# Schematic.net
KiCad netlist of a schematic drawn in Altium Designer
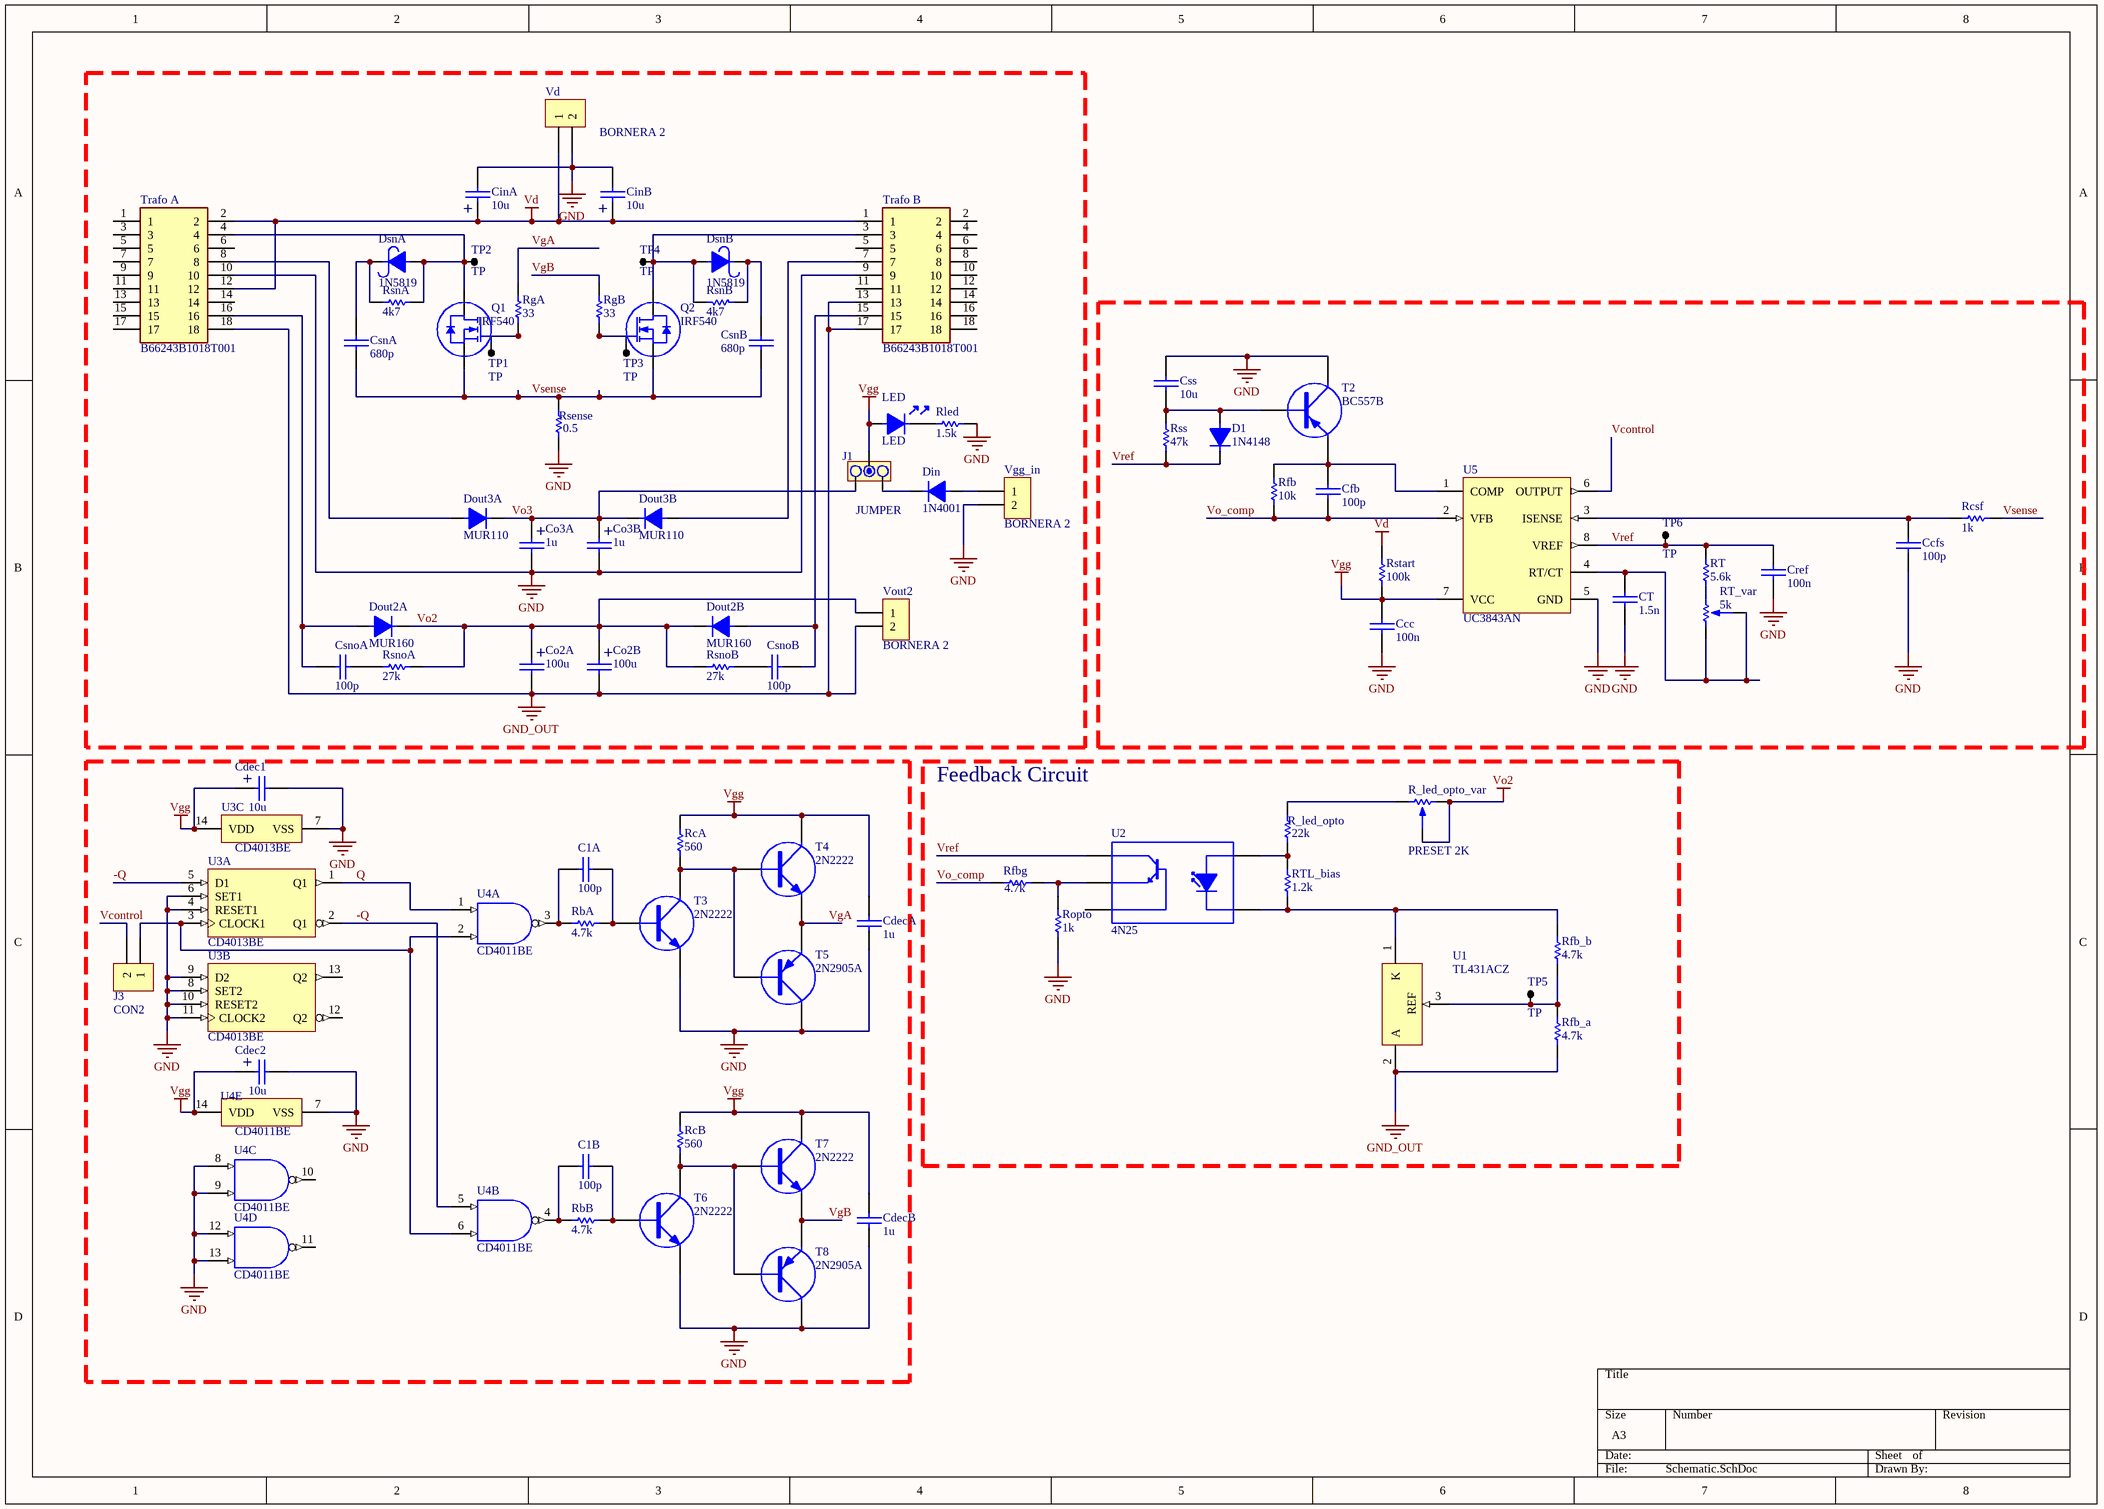
[diagram p0: Schematic.SchDoc]

(export (version "E")
  (design (tool "Eeschema 10.0.6"))
  (components
    (comp (ref "C1A") (value "100p") (footprint "CAP100") (libsource (lib "LIBEBAL Tobi") (part "CAP")))
    (comp (ref "C1B") (value "100p") (footprint "CAP100") (libsource (lib "LIBEBAL Tobi") (part "CAP")))
    (comp (ref "Ccc") (value "100n") (footprint "CAP100") (libsource (lib "LIBEBAL Tobi") (part "CAP")))
    (comp (ref "Ccfs") (value "100p") (footprint "CAP100") (libsource (lib "LIBEBAL Tobi") (part "CAP")))
    (comp (ref "Cdec1") (value "10u") (footprint "CAP100RP2") (libsource (lib "LIBEBAL") (part "CAPPOL")))
    (comp (ref "Cdec2") (value "10u") (footprint "CAP100RP2") (libsource (lib "LIBEBAL") (part "CAPPOL")))
    (comp (ref "CdecA") (value "1u") (footprint "CAP200") (libsource (lib "LIBEBAL Tobi") (part "CAP")))
    (comp (ref "CdecB") (value "1u") (footprint "CAP200") (libsource (lib "LIBEBAL Tobi") (part "CAP")))
    (comp (ref "Cfb") (value "100p") (footprint "CAP100") (libsource (lib "LIBEBAL Tobi") (part "CAP")))
    (comp (ref "CinA") (value "10u") (footprint "CAP100RP") (libsource (lib "LIBEBAL") (part "CAPPOL")))
    (comp (ref "CinB") (value "10u") (footprint "CAP100RP") (libsource (lib "LIBEBAL") (part "CAPPOL")))
    (comp (ref "Co2A") (value "100u") (footprint "CAP300RP") (libsource (lib "LIBEBAL") (part "CAPPOL")))
    (comp (ref "Co2B") (value "100u") (footprint "CAP300RP") (libsource (lib "LIBEBAL") (part "CAPPOL")))
    (comp (ref "Co3A") (value "1u") (footprint "CAP100RP") (libsource (lib "LIBEBAL") (part "CAPPOL")))
    (comp (ref "Co3B") (value "1u") (footprint "CAP100RP") (libsource (lib "LIBEBAL") (part "CAPPOL")))
    (comp (ref "Cref") (value "100n") (footprint "CAP100") (libsource (lib "LIBEBAL Tobi") (part "CAP")))
    (comp (ref "CsnA") (value "680p") (footprint "CAP200") (libsource (lib "LIBEBAL Tobi") (part "CAP")))
    (comp (ref "CsnB") (value "680p") (footprint "CAP200") (libsource (lib "LIBEBAL Tobi") (part "CAP")))
    (comp (ref "CsnoA") (value "100p") (footprint "CAP100") (libsource (lib "LIBEBAL Tobi") (part "CAP")))
    (comp (ref "CsnoB") (value "100p") (footprint "CAP100") (libsource (lib "LIBEBAL Tobi") (part "CAP")))
    (comp (ref "Css") (value "10u") (footprint "CAP100") (libsource (lib "LIBEBAL Tobi") (part "CAP")))
    (comp (ref "CT") (value "1.5n") (footprint "CAP100") (libsource (lib "LIBEBAL Tobi") (part "CAP")))
    (comp (ref "D1") (value "1N4148") (footprint "DO41") (libsource (lib "LIBEBAL") (part "DIODO")))
    (comp (ref "Din") (value "1N4001") (footprint "DO41") (libsource (lib "LIBEBAL") (part "DIODO")))
    (comp (ref "Dout2A") (value "MUR160") (footprint "DO41") (libsource (lib "LIBEBAL") (part "DIODO")))
    (comp (ref "Dout2B") (value "MUR160") (footprint "DO41") (libsource (lib "LIBEBAL") (part "DIODO")))
    (comp (ref "Dout3A") (value "MUR110") (footprint "DO41") (libsource (lib "LIBEBAL") (part "DIODO")))
    (comp (ref "Dout3B") (value "MUR110") (footprint "DO41") (libsource (lib "LIBEBAL") (part "DIODO")))
    (comp (ref "DsnA") (value "1N5819") (footprint "DO41") (libsource (lib "") (part "DIODO SCHOTTKY_1")))
    (comp (ref "DsnB")
      (value "1N5819")
      (footprint "DO41")
      (libsource (lib "LIBEBAL") (part "DIODO SCHOTTKY"))
    )
    (comp (ref "J1") (value "JUMPER") (footprint "JUMPER3") (libsource (lib "LIBEBAL") (part "JUMPER3")))
    (comp (ref "J3") (value "CON2") (footprint "SIP2") (libsource (lib "LIBEBAL") (part "CON2")))
    (comp (ref "LED") (value "LED") (footprint "LED3") (libsource (lib "LIBEBAL") (part "LED")))
    (comp (ref "Q1") (value "IRF540") (footprint "TO-220 V") (libsource (lib "LIBEBAL") (part "MOSFET N")))
    (comp (ref "Q2") (value "IRF540") (footprint "TO-220 V") (libsource (lib "LIBEBAL") (part "MOSFET N")))
    (comp (ref "RbA") (value "4.7k") (footprint "RES400") (libsource (lib "LIBEBAL Tobi") (part "RES")))
    (comp (ref "RbB") (value "4.7k") (footprint "RES400") (libsource (lib "LIBEBAL Tobi") (part "RES")))
    (comp (ref "RcA") (value "560") (footprint "RES400") (libsource (lib "LIBEBAL Tobi") (part "RES")))
    (comp (ref "RcB") (value "560") (footprint "RES400") (libsource (lib "LIBEBAL Tobi") (part "RES")))
    (comp (ref "Rcsf") (value "1k") (footprint "RES400") (libsource (lib "LIBEBAL Tobi") (part "RES")))
    (comp (ref "Rfb") (value "10k") (footprint "RES400") (libsource (lib "LIBEBAL Tobi") (part "RES")))
    (comp (ref "Rfbg") (value "4.7k") (footprint "RES400") (libsource (lib "LIBEBAL Tobi") (part "RES")))
    (comp (ref "Rfb_a") (value "4.7k") (footprint "RES400") (libsource (lib "LIBEBAL Tobi") (part "RES")))
    (comp (ref "Rfb_b") (value "4.7k") (footprint "RES400") (libsource (lib "LIBEBAL Tobi") (part "RES")))
    (comp (ref "RgA") (value "33") (footprint "RES400") (libsource (lib "LIBEBAL Tobi") (part "RES")))
    (comp (ref "RgB") (value "33") (footprint "RES400") (libsource (lib "LIBEBAL Tobi") (part "RES")))
    (comp (ref "Rled") (value "1.5k") (footprint "RES400") (libsource (lib "LIBEBAL Tobi") (part "RES")))
    (comp (ref "Ropto") (value "1k") (footprint "RES400") (libsource (lib "LIBEBAL Tobi") (part "RES")))
    (comp (ref "Rsense") (value "0.5") (footprint "RES400") (libsource (lib "LIBEBAL Tobi") (part "RES")))
    (comp (ref "RsnA") (value "4k7") (footprint "RES600") (libsource (lib "LIBEBAL Tobi") (part "RES")))
    (comp (ref "RsnB") (value "4k7") (footprint "RES600") (libsource (lib "LIBEBAL Tobi") (part "RES")))
    (comp (ref "RsnoA") (value "27k") (footprint "RES600") (libsource (lib "LIBEBAL Tobi") (part "RES")))
    (comp (ref "RsnoB") (value "27k") (footprint "RES600") (libsource (lib "LIBEBAL Tobi") (part "RES")))
    (comp (ref "Rss") (value "47k") (footprint "RES400") (libsource (lib "LIBEBAL Tobi") (part "RES")))
    (comp (ref "Rstart") (value "100k") (footprint "RES400") (libsource (lib "LIBEBAL Tobi") (part "RES")))
    (comp (ref "RT") (value "5.6k") (footprint "RES400") (libsource (lib "LIBEBAL Tobi") (part "RES")))
    (comp (ref "RTL_bias") (value "1.2k") (footprint "RES400") (libsource (lib "LIBEBAL Tobi") (part "RES")))
    (comp (ref "RT_var") (value "5k") (footprint "PRESET V") (libsource (lib "LIBEBAL Tobi") (part "PRESET")))
    (comp (ref "R_led_opto") (value "22k") (footprint "RES600") (libsource (lib "LIBEBAL Tobi") (part "RES")))
    (comp (ref "R_led_opto_var")
      (value "PRESET 2K")
      (footprint "PRESET H")
      (libsource (lib "LIBEBAL") (part "PRESET"))
    )
    (comp (ref "T2") (value "BC557B") (footprint "TO92") (libsource (lib "LIBEBAL") (part "TRANSISTOR PNP")))
    (comp (ref "T3") (value "2N2222") (footprint "TO92") (libsource (lib "LIBEBAL") (part "TRANSISTOR NPN")))
    (comp (ref "T4") (value "2N2222") (footprint "TO92") (libsource (lib "LIBEBAL") (part "TRANSISTOR NPN")))
    (comp (ref "T5") (value "2N2905A") (footprint "TO92") (libsource (lib "LIBEBAL") (part "TRANSISTOR PNP")))
    (comp (ref "T6") (value "2N2222") (footprint "TO92") (libsource (lib "LIBEBAL") (part "TRANSISTOR NPN")))
    (comp (ref "T7") (value "2N2222") (footprint "TO92") (libsource (lib "LIBEBAL") (part "TRANSISTOR NPN")))
    (comp (ref "T8") (value "2N2905A") (footprint "TO92") (libsource (lib "LIBEBAL") (part "TRANSISTOR PNP")))
    (comp (ref "TP1") (value "TP") (footprint "TPTH") (libsource (lib "LIBEBAL") (part "TP")))
    (comp (ref "TP2") (value "TP") (footprint "TPTH") (libsource (lib "LIBEBAL") (part "TP")))
    (comp (ref "TP3") (value "TP") (footprint "TPTH") (libsource (lib "LIBEBAL") (part "TP")))
    (comp (ref "TP4") (value "TP") (footprint "TPTH") (libsource (lib "LIBEBAL") (part "TP")))
    (comp (ref "TP5") (value "TP") (footprint "TPTH") (libsource (lib "LIBEBAL") (part "TP")))
    (comp (ref "TP6") (value "TP") (footprint "TPTH") (libsource (lib "LIBEBAL") (part "TP")))
    (comp (ref "Trafo A")
      (value "B66243B1018T001")
      (footprint "SamacSys:B66243B1018T001")
      (description "Inductor")
      (libsource (lib "*") (part "B66243B1018T001"))
    )
    (comp (ref "Trafo B")
      (value "B66243B1018T001")
      (footprint "SamacSys:B66243B1018T001")
      (description "Inductor")
      (libsource (lib "*") (part "B66243B1018T001"))
    )
    (comp (ref "U1")
      (value "TL431ACZ")
      (footprint "TO-92")
      (description "Programmable Voltage Reference, 2.5 to 36V, 3-Pin TO-92")
      (libsource (lib "Altium Content Vault") (part "PM-REF-431-SIL3"))
    )
    (comp (ref "U2") (value "4N25") (footprint "DIP6") (libsource (lib "LIBEBAL Tobi") (part "4N25")))
    (comp (ref "U3")
      (value "CD4013BE")
      (footprint "N0014A")
      (description "CMOS Dual D-Type Flip Flop, N0014A, TUBE")
      (fields
        (field (name "GENERIC PART NUMBER") "CD4013B")
        (field (name "MANUFACTURER") "Texas Instruments")
      )
      (libsource (lib "Altium Content Vault") (part "TI-CD4013B-14"))
    )
    (comp (ref "U4")
      (value "CD4011BE")
      (footprint "N0014A")
      (description "CMOS Quad 2-Input NAND Gate, N0014A, TUBE")
      (fields
        (field (name "MANUFACTURER") "Texas Instruments")
        (field (name "GENERIC PART NUMBER") "CD4011B")
      )
      (libsource (lib "Altium Content Vault") (part "TI-NAND-4-2IN-14_A"))
    )
    (comp (ref "U5")
      (value "UC3843AN")
      (footprint "P0008A")
      (fields (field (name "MANUFACTURER") "Texas Instruments"))
      (libsource (lib "Altium Content Vault") (part "TI-UC3843AP8"))
    )
    (comp (ref "Vd") (value "BORNERA 2") (footprint "BORNERA2") (libsource (lib "") (part "BORNERA 2_1")))
    (comp (ref "Vgg_in")
      (value "BORNERA 2")
      (footprint "BORNERA2")
      (libsource (lib "LIBEBAL") (part "BORNERA 2"))
    )
    (comp (ref "Vout2")
      (value "BORNERA 2")
      (footprint "BORNERA2")
      (libsource (lib "LIBEBAL") (part "BORNERA 2"))
    )
  )
  (nets
    (net (code "1") (name "/-Q") (class "Default")
      (node (ref "U3") (pin "2") (pinfunction "Q1_2") (pintype "output"))
      (node (ref "U3") (pin "5") (pinfunction "D1_5") (pintype "input"))
      (node (ref "U4") (pin "5") (pinfunction "C_5") (pintype "input"))
    )
    (net (code "2") (name "/Q") (class "Default")
      (node (ref "U3") (pin "1") (pinfunction "Q1_1") (pintype "output"))
      (node (ref "U4") (pin "1") (pinfunction "A_1") (pintype "input"))
    )
    (net (code "3") (name "/Vcontrol") (class "Default")
      (node (ref "J3") (pin "2") (pinfunction "2_2") (pintype "passive"))
      (node (ref "U5") (pin "6") (pinfunction "OUTPUT_6") (pintype "output"))
    )
    (net (code "4") (name "/VgA") (class "Default")
      (node (ref "RgA") (pin "1") (pinfunction "1_1") (pintype "passive"))
      (node (ref "T4") (pin "3") (pinfunction "E_3") (pintype "passive"))
      (node (ref "T5") (pin "3") (pinfunction "E_3") (pintype "passive"))
    )
    (net (code "5") (name "/VgB") (class "Default")
      (node (ref "RgB") (pin "1") (pinfunction "1_1") (pintype "passive"))
      (node (ref "T7") (pin "3") (pinfunction "E_3") (pintype "passive"))
      (node (ref "T8") (pin "3") (pinfunction "E_3") (pintype "passive"))
    )
    (net (code "6") (name "/Vo3") (class "Default")
      (node (ref "Co3A") (pin "1") (pinfunction "1_1") (pintype "passive"))
      (node (ref "Co3B") (pin "1") (pinfunction "1_1") (pintype "passive"))
      (node (ref "Dout3A") (pin "2") (pinfunction "2_2") (pintype "passive"))
      (node (ref "Dout3B") (pin "2") (pinfunction "2_2") (pintype "passive"))
      (node (ref "J1") (pin "1") (pinfunction "1_1") (pintype "passive"))
    )
    (net (code "7") (name "/Vo_comp") (class "Default")
      (node (ref "Cfb") (pin "1") (pinfunction "1_1") (pintype "passive"))
      (node (ref "Rfb") (pin "1") (pinfunction "1_1") (pintype "passive"))
      (node (ref "Rfbg") (pin "1") (pinfunction "1_1") (pintype "passive"))
      (node (ref "U5") (pin "2") (pinfunction "VFB_2") (pintype "input"))
    )
    (net (code "8") (name "/Vref") (class "Default")
      (node (ref "Cref") (pin "2") (pinfunction "2_2") (pintype "passive"))
      (node (ref "D1") (pin "2") (pinfunction "2_2") (pintype "passive"))
      (node (ref "RT") (pin "2") (pinfunction "2_2") (pintype "passive"))
      (node (ref "Rss") (pin "2") (pinfunction "2_2") (pintype "passive"))
      (node (ref "TP6") (pin "1") (pinfunction "1_1") (pintype "passive"))
      (node (ref "U2") (pin "5") (pinfunction "C_5") (pintype "passive"))
      (node (ref "U5") (pin "8") (pinfunction "VREF_8") (pintype "output"))
    )
    (net (code "9") (name "/Vsense") (class "Default")
      (node (ref "CsnA") (pin "1") (pinfunction "1_1") (pintype "passive"))
      (node (ref "CsnB") (pin "1") (pinfunction "1_1") (pintype "passive"))
      (node (ref "Q1") (pin "3") (pinfunction "S_3") (pintype "passive"))
      (node (ref "Q2") (pin "3") (pinfunction "S_3") (pintype "passive"))
      (node (ref "Rcsf") (pin "1") (pinfunction "1_1") (pintype "passive"))
      (node (ref "Rsense") (pin "1") (pinfunction "1_1") (pintype "passive"))
    )
    (net (code "10") (name "GND") (class "Default")
      (node (ref "CT") (pin "1") (pinfunction "1_1") (pintype "passive"))
      (node (ref "Ccc") (pin "1") (pinfunction "1_1") (pintype "passive"))
      (node (ref "Ccfs") (pin "1") (pinfunction "1_1") (pintype "passive"))
      (node (ref "Cdec1") (pin "2") (pinfunction "2_2") (pintype "passive"))
      (node (ref "Cdec2") (pin "2") (pinfunction "2_2") (pintype "passive"))
      (node (ref "CdecA") (pin "1") (pinfunction "1_1") (pintype "passive"))
      (node (ref "CdecB") (pin "1") (pinfunction "1_1") (pintype "passive"))
      (node (ref "CinA") (pin "2") (pinfunction "2_2") (pintype "passive"))
      (node (ref "CinB") (pin "2") (pinfunction "2_2") (pintype "passive"))
      (node (ref "Co3A") (pin "2") (pinfunction "2_2") (pintype "passive"))
      (node (ref "Co3B") (pin "2") (pinfunction "2_2") (pintype "passive"))
      (node (ref "Cref") (pin "1") (pinfunction "1_1") (pintype "passive"))
      (node (ref "Css") (pin "1") (pinfunction "1_1") (pintype "passive"))
      (node (ref "Rled") (pin "1") (pinfunction "1_1") (pintype "passive"))
      (node (ref "Ropto") (pin "1") (pinfunction "1_1") (pintype "passive"))
      (node (ref "Rsense") (pin "2") (pinfunction "2_2") (pintype "passive"))
      (node (ref "T2") (pin "2") (pinfunction "C_2") (pintype "passive"))
      (node (ref "T3") (pin "3") (pinfunction "E_3") (pintype "passive"))
      (node (ref "T5") (pin "2") (pinfunction "C_2") (pintype "passive"))
      (node (ref "T6") (pin "3") (pinfunction "E_3") (pintype "passive"))
      (node (ref "T8") (pin "2") (pinfunction "C_2") (pintype "passive"))
      (node (ref "Trafo A") (pin "10") (pinfunction "10_10") (pintype "passive"))
      (node (ref "Trafo B") (pin "9") (pinfunction "9_9") (pintype "passive"))
      (node (ref "U3") (pin "10") (pinfunction "RESET2_10") (pintype "input"))
      (node (ref "U3") (pin "11") (pinfunction "CLOCK2_11") (pintype "input"))
      (node (ref "U3") (pin "4") (pinfunction "RESET1_4") (pintype "input"))
      (node (ref "U3") (pin "6") (pinfunction "SET1_6") (pintype "input"))
      (node (ref "U3") (pin "7") (pinfunction "VSS_7") (pintype "power_in"))
      (node (ref "U3") (pin "8") (pinfunction "SET2_8") (pintype "input"))
      (node (ref "U3") (pin "9") (pinfunction "D2_9") (pintype "input"))
      (node (ref "U4") (pin "12") (pinfunction "G_12") (pintype "input"))
      (node (ref "U4") (pin "13") (pinfunction "H_13") (pintype "input"))
      (node (ref "U4") (pin "7") (pinfunction "VSS_7") (pintype "power_in"))
      (node (ref "U4") (pin "8") (pinfunction "E_8") (pintype "input"))
      (node (ref "U4") (pin "9") (pinfunction "F_9") (pintype "input"))
      (node (ref "U5") (pin "5") (pinfunction "GND_5") (pintype "power_in"))
      (node (ref "Vd") (pin "2") (pinfunction "2_2") (pintype "passive"))
      (node (ref "Vgg_in") (pin "2") (pinfunction "2_2") (pintype "passive"))
    )
    (net (code "11") (name "GND_OUT") (class "Default")
      (node (ref "Co2A") (pin "2") (pinfunction "2_2") (pintype "passive"))
      (node (ref "Co2B") (pin "2") (pinfunction "2_2") (pintype "passive"))
      (node (ref "Rfb_a") (pin "1") (pinfunction "1_1") (pintype "passive"))
      (node (ref "Trafo A") (pin "18") (pinfunction "18_18") (pintype "passive"))
      (node (ref "Trafo B") (pin "13") (pinfunction "13_13") (pintype "passive"))
      (node (ref "Trafo B") (pin "17") (pinfunction "17_17") (pintype "passive"))
      (node (ref "U1") (pin "2") (pinfunction "A_2") (pintype "passive"))
      (node (ref "Vout2") (pin "2") (pinfunction "2_2") (pintype "passive"))
    )
    (net (code "12") (name "Net-(CsnA-Pad2)") (class "Default")
      (node (ref "CsnA") (pin "2") (pinfunction "2_2") (pintype "passive"))
      (node (ref "DsnA") (pin "2") (pinfunction "2_2") (pintype "passive"))
      (node (ref "RsnA") (pin "1") (pinfunction "1_1") (pintype "passive"))
    )
    (net (code "13") (name "Net-(CsnB-Pad2)") (class "Default")
      (node (ref "CsnB") (pin "2") (pinfunction "2_2") (pintype "passive"))
      (node (ref "DsnB") (pin "2") (pinfunction "2_2") (pintype "passive"))
      (node (ref "RsnB") (pin "1") (pinfunction "1_1") (pintype "passive"))
    )
    (net (code "14") (name "Net-(CsnoA-Pad1)") (class "Default")
      (node (ref "CsnoA") (pin "1") (pinfunction "1_1") (pintype "passive"))
      (node (ref "Dout2A") (pin "1") (pinfunction "1_1") (pintype "passive"))
      (node (ref "Trafo A") (pin "16") (pinfunction "16_16") (pintype "passive"))
    )
    (net (code "15") (name "Net-(CsnoA-Pad2)") (class "Default")
      (node (ref "CsnoA") (pin "2") (pinfunction "2_2") (pintype "passive"))
      (node (ref "RsnoA") (pin "1") (pinfunction "1_1") (pintype "passive"))
    )
    (net (code "16") (name "Net-(CsnoB-Pad1)") (class "Default")
      (node (ref "CsnoB") (pin "1") (pinfunction "1_1") (pintype "passive"))
      (node (ref "Dout2B") (pin "1") (pinfunction "1_1") (pintype "passive"))
      (node (ref "Trafo B") (pin "15") (pinfunction "15_15") (pintype "passive"))
    )
    (net (code "17") (name "Net-(CsnoB-Pad2)") (class "Default")
      (node (ref "CsnoB") (pin "2") (pinfunction "2_2") (pintype "passive"))
      (node (ref "RsnoB") (pin "1") (pinfunction "1_1") (pintype "passive"))
    )
    (net (code "18") (name "Net-(Din-Pad1)") (class "Default")
      (node (ref "Din") (pin "1") (pinfunction "1_1") (pintype "passive"))
      (node (ref "Vgg_in") (pin "1") (pinfunction "1_1") (pintype "passive"))
    )
    (net (code "19") (name "Net-(Din-Pad2)") (class "Default")
      (node (ref "Din") (pin "2") (pinfunction "2_2") (pintype "passive"))
      (node (ref "J1") (pin "3") (pinfunction "3_3") (pintype "passive"))
    )
    (net (code "20") (name "Net-(Dout3A-Pad1)") (class "Default")
      (node (ref "Dout3A") (pin "1") (pinfunction "1_1") (pintype "passive"))
      (node (ref "Trafo A") (pin "8") (pinfunction "8_8") (pintype "passive"))
    )
    (net (code "21") (name "Net-(Dout3B-Pad1)") (class "Default")
      (node (ref "Dout3B") (pin "1") (pinfunction "1_1") (pintype "passive"))
      (node (ref "Trafo B") (pin "7") (pinfunction "7_7") (pintype "passive"))
    )
    (net (code "22") (name "Net-(LED-Pad2)") (class "Default")
      (node (ref "LED") (pin "2") (pinfunction "2_2") (pintype "passive"))
      (node (ref "Rled") (pin "2") (pinfunction "2_2") (pintype "passive"))
    )
    (net (code "23") (name "Net-(Q1-D)") (class "Default")
      (node (ref "DsnA") (pin "1") (pinfunction "1_1") (pintype "passive"))
      (node (ref "Q1") (pin "2") (pinfunction "D_2") (pintype "passive"))
      (node (ref "RsnA") (pin "2") (pinfunction "2_2") (pintype "passive"))
      (node (ref "TP2") (pin "1") (pinfunction "1_1") (pintype "passive"))
      (node (ref "Trafo A") (pin "4") (pinfunction "4_4") (pintype "passive"))
    )
    (net (code "24") (name "Net-(Q1-G)") (class "Default")
      (node (ref "Q1") (pin "1") (pinfunction "G_1") (pintype "passive"))
      (node (ref "RgA") (pin "2") (pinfunction "2_2") (pintype "passive"))
      (node (ref "TP1") (pin "1") (pinfunction "1_1") (pintype "passive"))
    )
    (net (code "25") (name "Net-(Q2-D)") (class "Default")
      (node (ref "DsnB") (pin "1") (pinfunction "1_1") (pintype "passive"))
      (node (ref "Q2") (pin "2") (pinfunction "D_2") (pintype "passive"))
      (node (ref "RsnB") (pin "2") (pinfunction "2_2") (pintype "passive"))
      (node (ref "TP4") (pin "1") (pinfunction "1_1") (pintype "passive"))
      (node (ref "Trafo B") (pin "3") (pinfunction "3_3") (pintype "passive"))
    )
    (net (code "26") (name "Net-(Q2-G)") (class "Default")
      (node (ref "Q2") (pin "1") (pinfunction "G_1") (pintype "passive"))
      (node (ref "RgB") (pin "2") (pinfunction "2_2") (pintype "passive"))
      (node (ref "TP3") (pin "1") (pinfunction "1_1") (pintype "passive"))
    )
    (net (code "27") (name "Net-(RT-Pad1)") (class "Default")
      (node (ref "RT") (pin "1") (pinfunction "1_1") (pintype "passive"))
      (node (ref "RT_var") (pin "1") (pinfunction "1_1") (pintype "passive"))
    )
    (net (code "28") (name "Net-(R_led_opto-Pad2)") (class "Default")
      (node (ref "R_led_opto") (pin "2") (pinfunction "2_2") (pintype "passive"))
      (node (ref "R_led_opto_var") (pin "3") (pinfunction "3_3") (pintype "passive"))
    )
    (net (code "29") (name "Net-(T2-B)") (class "Default")
      (node (ref "Css") (pin "2") (pinfunction "2_2") (pintype "passive"))
      (node (ref "D1") (pin "1") (pinfunction "1_1") (pintype "passive"))
      (node (ref "Rss") (pin "1") (pinfunction "1_1") (pintype "passive"))
      (node (ref "T2") (pin "1") (pinfunction "B_1") (pintype "passive"))
    )
    (net (code "30") (name "Net-(T2-E)") (class "Default")
      (node (ref "Cfb") (pin "2") (pinfunction "2_2") (pintype "passive"))
      (node (ref "Rfb") (pin "2") (pinfunction "2_2") (pintype "passive"))
      (node (ref "T2") (pin "3") (pinfunction "E_3") (pintype "passive"))
      (node (ref "U5") (pin "1") (pinfunction "COMP_1") (pintype "passive"))
    )
    (net (code "31") (name "Net-(T3-B)") (class "Default")
      (node (ref "C1A") (pin "2") (pinfunction "2_2") (pintype "passive"))
      (node (ref "RbA") (pin "1") (pinfunction "1_1") (pintype "passive"))
      (node (ref "T3") (pin "1") (pinfunction "B_1") (pintype "passive"))
    )
    (net (code "32") (name "Net-(T3-C)") (class "Default")
      (node (ref "RcA") (pin "2") (pinfunction "2_2") (pintype "passive"))
      (node (ref "T3") (pin "2") (pinfunction "C_2") (pintype "passive"))
      (node (ref "T4") (pin "1") (pinfunction "B_1") (pintype "passive"))
      (node (ref "T5") (pin "1") (pinfunction "B_1") (pintype "passive"))
    )
    (net (code "33") (name "Net-(T6-B)") (class "Default")
      (node (ref "C1B") (pin "2") (pinfunction "2_2") (pintype "passive"))
      (node (ref "RbB") (pin "1") (pinfunction "1_1") (pintype "passive"))
      (node (ref "T6") (pin "1") (pinfunction "B_1") (pintype "passive"))
    )
    (net (code "34") (name "Net-(T6-C)") (class "Default")
      (node (ref "RcB") (pin "2") (pinfunction "2_2") (pintype "passive"))
      (node (ref "T6") (pin "2") (pinfunction "C_2") (pintype "passive"))
      (node (ref "T7") (pin "1") (pinfunction "B_1") (pintype "passive"))
      (node (ref "T8") (pin "1") (pinfunction "B_1") (pintype "passive"))
    )
    (net (code "35") (name "Net-(U1-K)") (class "Default")
      (node (ref "RTL_bias") (pin "1") (pinfunction "1_1") (pintype "passive"))
      (node (ref "Rfb_b") (pin "2") (pinfunction "2_2") (pintype "passive"))
      (node (ref "U1") (pin "1") (pinfunction "K_1") (pintype "passive"))
      (node (ref "U2") (pin "2") (pinfunction "K_2") (pintype "passive"))
    )
    (net (code "36") (name "Net-(U1-REF)") (class "Default")
      (node (ref "Rfb_a") (pin "2") (pinfunction "2_2") (pintype "passive"))
      (node (ref "Rfb_b") (pin "1") (pinfunction "1_1") (pintype "passive"))
      (node (ref "TP5") (pin "1") (pinfunction "1_1") (pintype "passive"))
      (node (ref "U1") (pin "3") (pinfunction "REF_3") (pintype "input"))
    )
    (net (code "37") (name "Net-(U2-A)") (class "Default")
      (node (ref "RTL_bias") (pin "2") (pinfunction "2_2") (pintype "passive"))
      (node (ref "R_led_opto") (pin "1") (pinfunction "1_1") (pintype "passive"))
      (node (ref "U2") (pin "1") (pinfunction "A_1") (pintype "passive"))
    )
    (net (code "38") (name "Net-(U2-E)") (class "Default")
      (node (ref "Rfbg") (pin "2") (pinfunction "2_2") (pintype "passive"))
      (node (ref "Ropto") (pin "2") (pinfunction "2_2") (pintype "passive"))
      (node (ref "U2") (pin "4") (pinfunction "E_4") (pintype "passive"))
    )
    (net (code "39") (name "Net-(U3A-CLOCK1)") (class "Default")
      (node (ref "J3") (pin "1") (pinfunction "1_1") (pintype "passive"))
      (node (ref "U3") (pin "3") (pinfunction "CLOCK1_3") (pintype "input"))
      (node (ref "U4") (pin "2") (pinfunction "B_2") (pintype "input"))
      (node (ref "U4") (pin "6") (pinfunction "D_6") (pintype "input"))
    )
    (net (code "40") (name "Net-(U4A-J)") (class "Default")
      (node (ref "C1A") (pin "1") (pinfunction "1_1") (pintype "passive"))
      (node (ref "RbA") (pin "2") (pinfunction "2_2") (pintype "passive"))
      (node (ref "U4") (pin "3") (pinfunction "J_3") (pintype "output"))
    )
    (net (code "41") (name "Net-(U4B-K)") (class "Default")
      (node (ref "C1B") (pin "1") (pinfunction "1_1") (pintype "passive"))
      (node (ref "RbB") (pin "2") (pinfunction "2_2") (pintype "passive"))
      (node (ref "U4") (pin "4") (pinfunction "K_4") (pintype "output"))
    )
    (net (code "42") (name "Net-(U5-ISENSE)") (class "Default")
      (node (ref "Ccfs") (pin "2") (pinfunction "2_2") (pintype "passive"))
      (node (ref "Rcsf") (pin "2") (pinfunction "2_2") (pintype "passive"))
      (node (ref "U5") (pin "3") (pinfunction "ISENSE_3") (pintype "input"))
    )
    (net (code "43") (name "Net-(U5-RT{slash}CT)") (class "Default")
      (node (ref "CT") (pin "2") (pinfunction "2_2") (pintype "passive"))
      (node (ref "RT_var") (pin "2") (pinfunction "2_2") (pintype "passive"))
      (node (ref "RT_var") (pin "3") (pinfunction "3_3") (pintype "passive"))
      (node (ref "U5") (pin "4") (pinfunction "RT/CT_4") (pintype "passive"))
    )
    (net (code "44") (name "Vd") (class "Default")
      (node (ref "CinA") (pin "1") (pinfunction "1_1") (pintype "passive"))
      (node (ref "CinB") (pin "1") (pinfunction "1_1") (pintype "passive"))
      (node (ref "Rstart") (pin "2") (pinfunction "2_2") (pintype "passive"))
      (node (ref "Trafo A") (pin "12") (pinfunction "12_12") (pintype "passive"))
      (node (ref "Trafo A") (pin "2") (pinfunction "2_2") (pintype "passive"))
      (node (ref "Trafo B") (pin "1") (pinfunction "1_1") (pintype "passive"))
      (node (ref "Vd") (pin "1") (pinfunction "1_1") (pintype "passive"))
    )
    (net (code "45") (name "Vgg") (class "Default")
      (node (ref "Ccc") (pin "2") (pinfunction "2_2") (pintype "passive"))
      (node (ref "Cdec1") (pin "1") (pinfunction "1_1") (pintype "passive"))
      (node (ref "Cdec2") (pin "1") (pinfunction "1_1") (pintype "passive"))
      (node (ref "CdecA") (pin "2") (pinfunction "2_2") (pintype "passive"))
      (node (ref "CdecB") (pin "2") (pinfunction "2_2") (pintype "passive"))
      (node (ref "J1") (pin "2") (pinfunction "2_2") (pintype "passive"))
      (node (ref "LED") (pin "1") (pinfunction "1_1") (pintype "passive"))
      (node (ref "RcA") (pin "1") (pinfunction "1_1") (pintype "passive"))
      (node (ref "RcB") (pin "1") (pinfunction "1_1") (pintype "passive"))
      (node (ref "Rstart") (pin "1") (pinfunction "1_1") (pintype "passive"))
      (node (ref "T4") (pin "2") (pinfunction "C_2") (pintype "passive"))
      (node (ref "T7") (pin "2") (pinfunction "C_2") (pintype "passive"))
      (node (ref "U3") (pin "14") (pinfunction "VDD_14") (pintype "power_in"))
      (node (ref "U4") (pin "14") (pinfunction "VDD_14") (pintype "power_in"))
      (node (ref "U5") (pin "7") (pinfunction "VCC_7") (pintype "power_in"))
    )
    (net (code "46") (name "Vo2") (class "Default")
      (node (ref "Co2A") (pin "1") (pinfunction "1_1") (pintype "passive"))
      (node (ref "Co2B") (pin "1") (pinfunction "1_1") (pintype "passive"))
      (node (ref "Dout2A") (pin "2") (pinfunction "2_2") (pintype "passive"))
      (node (ref "Dout2B") (pin "2") (pinfunction "2_2") (pintype "passive"))
      (node (ref "R_led_opto_var") (pin "1") (pinfunction "1_1") (pintype "passive"))
      (node (ref "R_led_opto_var") (pin "2") (pinfunction "2_2") (pintype "passive"))
      (node (ref "RsnoA") (pin "2") (pinfunction "2_2") (pintype "passive"))
      (node (ref "RsnoB") (pin "2") (pinfunction "2_2") (pintype "passive"))
      (node (ref "Vout2") (pin "1") (pinfunction "1_1") (pintype "passive"))
    )
    (net (code "47") (name "unconnected-(Trafo A-Pad1)") (class "Default")
      (node (ref "Trafo A") (pin "1") (pinfunction "1_1") (pintype "passive"))
    )
    (net (code "48") (name "unconnected-(Trafo A-Pad3)") (class "Default")
      (node (ref "Trafo A") (pin "3") (pinfunction "3_3") (pintype "passive"))
    )
    (net (code "49") (name "unconnected-(Trafo A-Pad5)") (class "Default")
      (node (ref "Trafo A") (pin "5") (pinfunction "5_5") (pintype "passive"))
    )
    (net (code "50") (name "unconnected-(Trafo A-Pad6)") (class "Default")
      (node (ref "Trafo A") (pin "6") (pinfunction "6_6") (pintype "passive"))
    )
    (net (code "51") (name "unconnected-(Trafo A-Pad7)") (class "Default")
      (node (ref "Trafo A") (pin "7") (pinfunction "7_7") (pintype "passive"))
    )
    (net (code "52") (name "unconnected-(Trafo A-Pad9)") (class "Default")
      (node (ref "Trafo A") (pin "9") (pinfunction "9_9") (pintype "passive"))
    )
    (net (code "53") (name "unconnected-(Trafo A-Pad11)") (class "Default")
      (node (ref "Trafo A") (pin "11") (pinfunction "11_11") (pintype "passive"))
    )
    (net (code "54") (name "unconnected-(Trafo A-Pad13)") (class "Default")
      (node (ref "Trafo A") (pin "13") (pinfunction "13_13") (pintype "passive"))
    )
    (net (code "55") (name "unconnected-(Trafo A-Pad14)") (class "Default")
      (node (ref "Trafo A") (pin "14") (pinfunction "14_14") (pintype "passive"))
    )
    (net (code "56") (name "unconnected-(Trafo A-Pad15)") (class "Default")
      (node (ref "Trafo A") (pin "15") (pinfunction "15_15") (pintype "passive"))
    )
    (net (code "57") (name "unconnected-(Trafo A-Pad17)") (class "Default")
      (node (ref "Trafo A") (pin "17") (pinfunction "17_17") (pintype "passive"))
    )
    (net (code "58") (name "unconnected-(Trafo B-Pad2)") (class "Default")
      (node (ref "Trafo B") (pin "2") (pinfunction "2_2") (pintype "passive"))
    )
    (net (code "59") (name "unconnected-(Trafo B-Pad4)") (class "Default")
      (node (ref "Trafo B") (pin "4") (pinfunction "4_4") (pintype "passive"))
    )
    (net (code "60") (name "unconnected-(Trafo B-Pad5)") (class "Default")
      (node (ref "Trafo B") (pin "5") (pinfunction "5_5") (pintype "passive"))
    )
    (net (code "61") (name "unconnected-(Trafo B-Pad6)") (class "Default")
      (node (ref "Trafo B") (pin "6") (pinfunction "6_6") (pintype "passive"))
    )
    (net (code "62") (name "unconnected-(Trafo B-Pad8)") (class "Default")
      (node (ref "Trafo B") (pin "8") (pinfunction "8_8") (pintype "passive"))
    )
    (net (code "63") (name "unconnected-(Trafo B-Pad10)") (class "Default")
      (node (ref "Trafo B") (pin "10") (pinfunction "10_10") (pintype "passive"))
    )
    (net (code "64") (name "unconnected-(Trafo B-Pad11)") (class "Default")
      (node (ref "Trafo B") (pin "11") (pinfunction "11_11") (pintype "passive"))
    )
    (net (code "65") (name "unconnected-(Trafo B-Pad12)") (class "Default")
      (node (ref "Trafo B") (pin "12") (pinfunction "12_12") (pintype "passive"))
    )
    (net (code "66") (name "unconnected-(Trafo B-Pad14)") (class "Default")
      (node (ref "Trafo B") (pin "14") (pinfunction "14_14") (pintype "passive"))
    )
    (net (code "67") (name "unconnected-(Trafo B-Pad16)") (class "Default")
      (node (ref "Trafo B") (pin "16") (pinfunction "16_16") (pintype "passive"))
    )
    (net (code "68") (name "unconnected-(Trafo B-Pad18)") (class "Default")
      (node (ref "Trafo B") (pin "18") (pinfunction "18_18") (pintype "passive"))
    )
    (net (code "69") (name "unconnected-(U2-B-Pad6)") (class "Default")
      (node (ref "U2") (pin "6") (pinfunction "B_6") (pintype "passive"))
    )
    (net (code "70") (name "unconnected-(U3B-Q2-Pad12)") (class "Default")
      (node (ref "U3") (pin "12") (pinfunction "Q2_12") (pintype "output"))
    )
    (net (code "71") (name "unconnected-(U3B-Q2-Pad13)") (class "Default")
      (node (ref "U3") (pin "13") (pinfunction "Q2_13") (pintype "output"))
    )
    (net (code "72") (name "unconnected-(U4C-L-Pad10)") (class "Default")
      (node (ref "U4") (pin "10") (pinfunction "L_10") (pintype "output"))
    )
    (net (code "73") (name "unconnected-(U4D-M-Pad11)") (class "Default")
      (node (ref "U4") (pin "11") (pinfunction "M_11") (pintype "output"))
    )
  )
)
